# jetson-orin-baseboard.net
KiCad netlist of a schematic drawn in Altium Designer
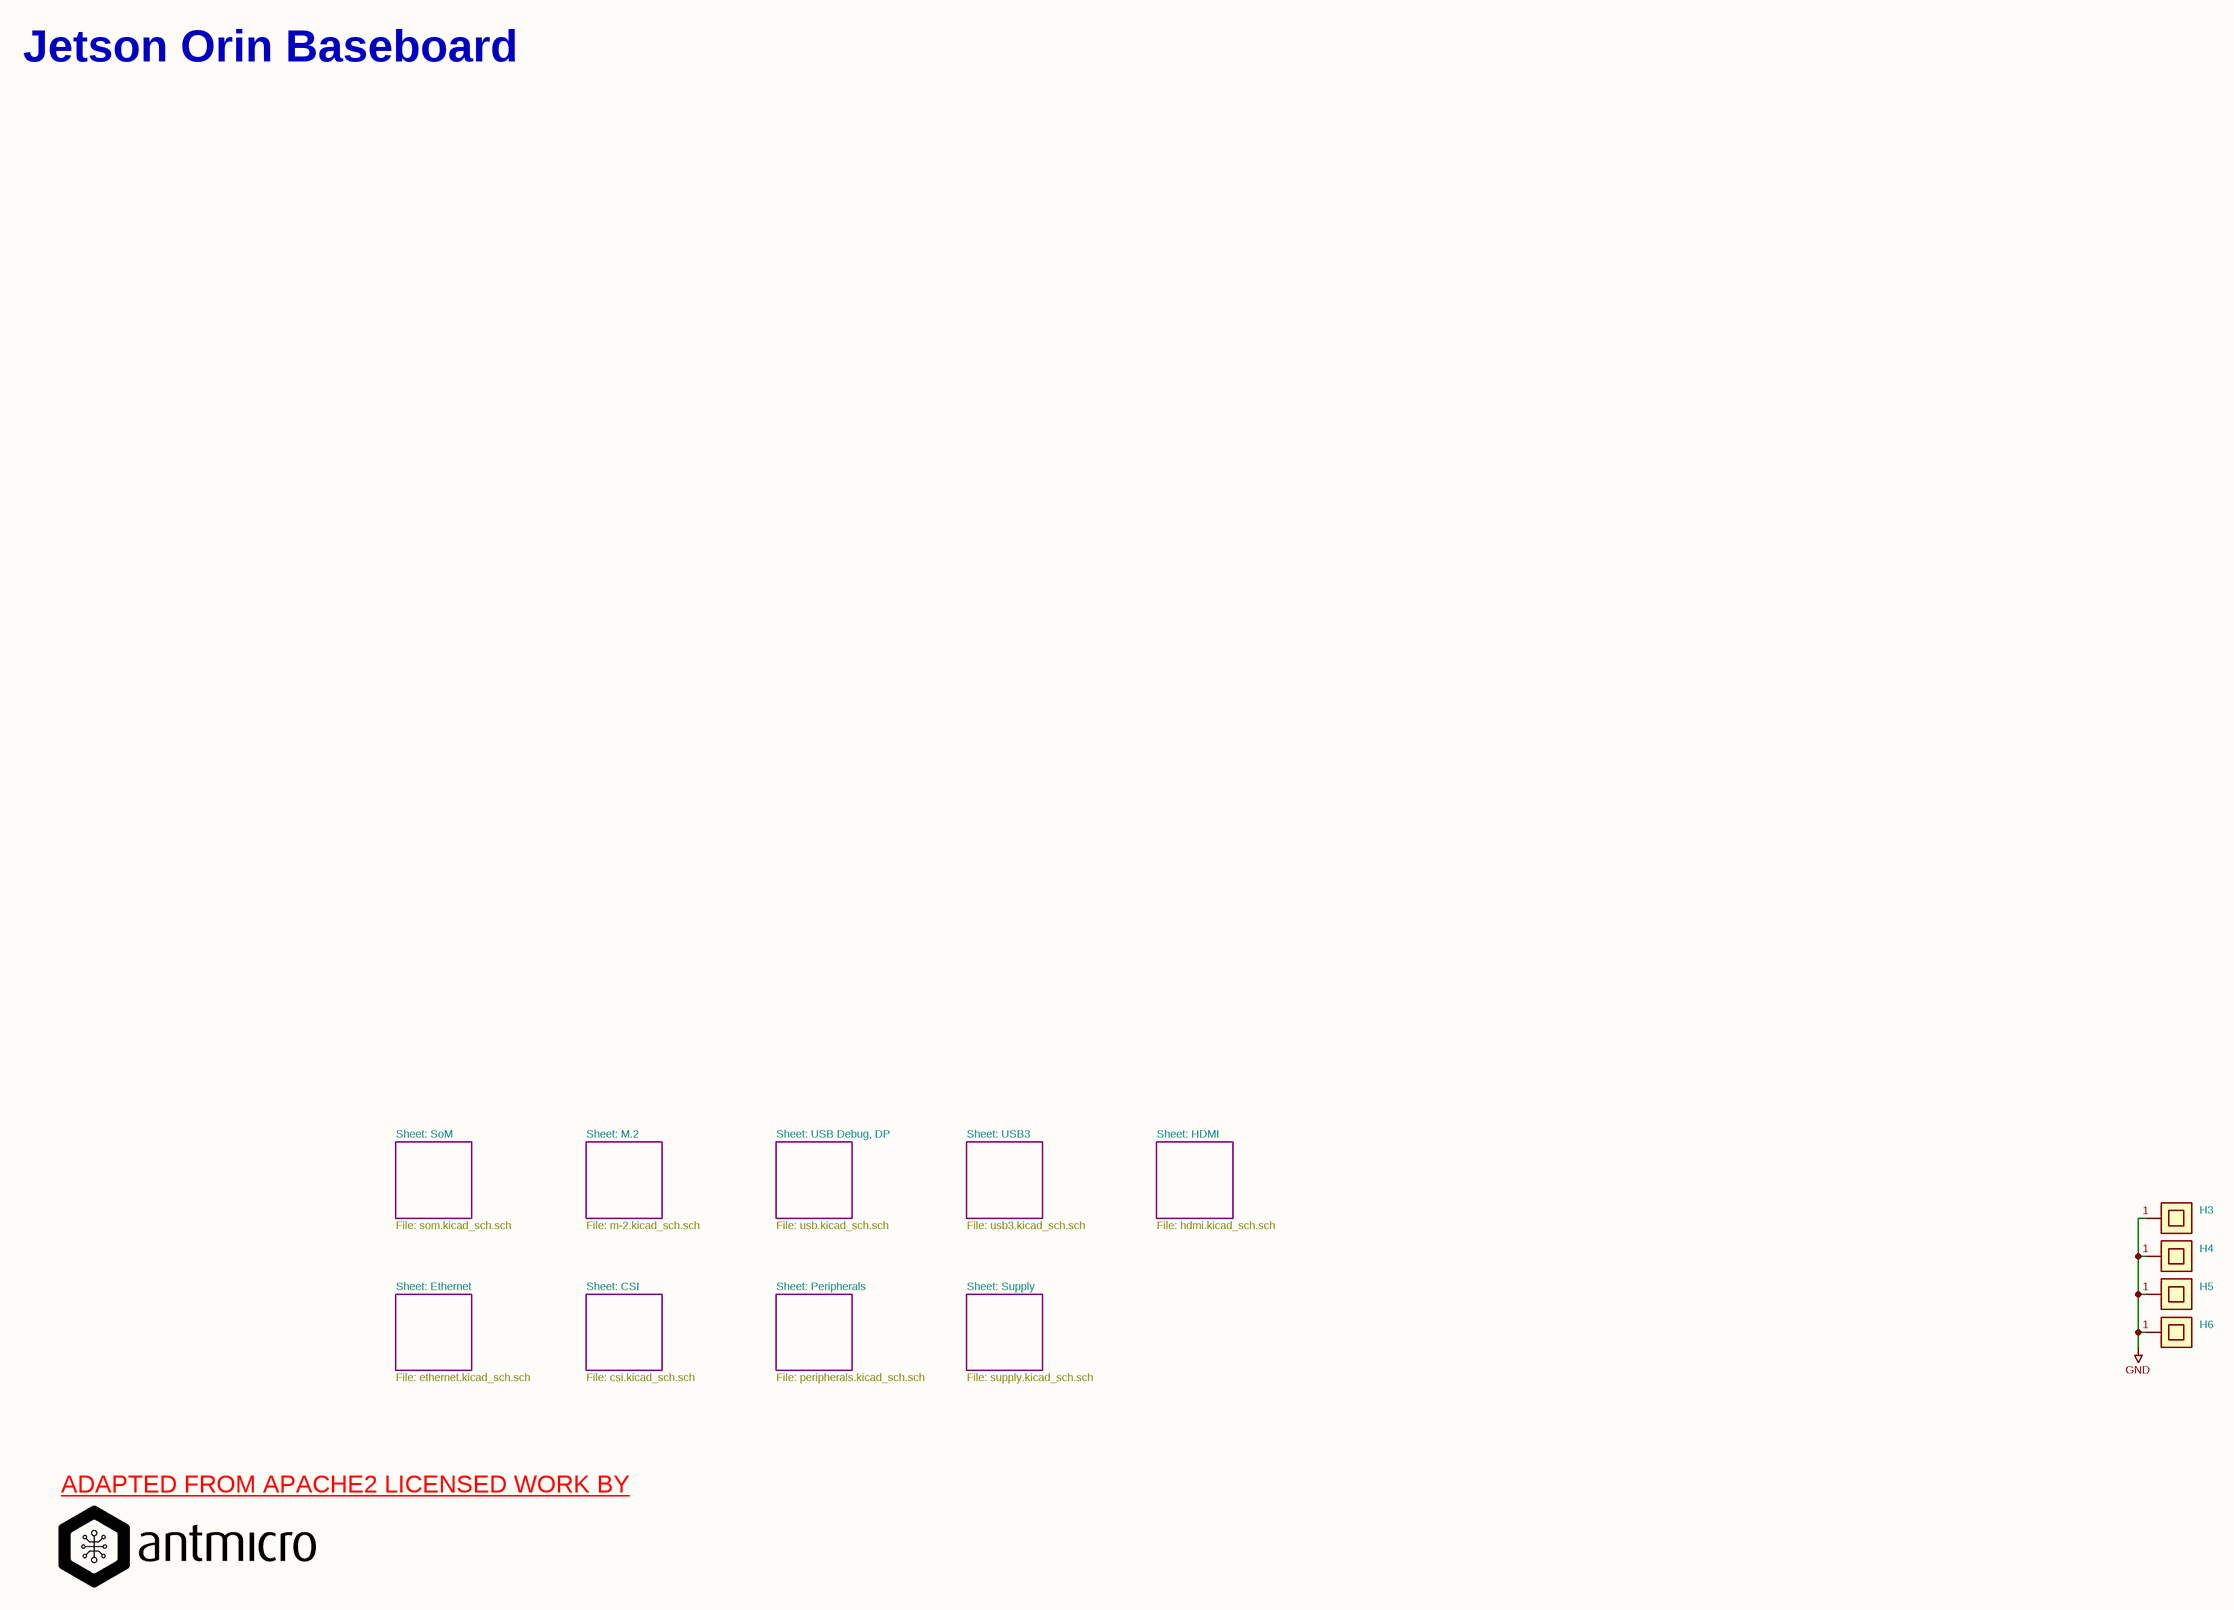
[diagram p0: jetson-orin-baseboard.SchDoc]

(export (version "E")
  (design (tool "Eeschema 10.0.6"))
  (components
    (comp (ref "H3")
      (value "9774065151R")
      (footprint "Spacer_Drill3.7mm_H6.5mm_9774065151R")
      (fields (field (name "AUTHOR") "Antmicro"))
      (libsource (lib "antmicroMechanicalParts") (part "Spacer_Drill3.7mm_H6.5mm_9774065151R"))
    )
    (comp (ref "H4")
      (value "9774065151R")
      (footprint "Spacer_Drill3.7mm_H6.5mm_9774065151R")
      (fields (field (name "AUTHOR") "Antmicro"))
      (libsource (lib "antmicroMechanicalParts") (part "Spacer_Drill3.7mm_H6.5mm_9774065151R"))
    )
    (comp (ref "H5")
      (value "9774065151R")
      (footprint "Spacer_Drill3.7mm_H6.5mm_9774065151R")
      (fields (field (name "AUTHOR") "Antmicro"))
      (libsource (lib "antmicroMechanicalParts") (part "Spacer_Drill3.7mm_H6.5mm_9774065151R"))
    )
    (comp (ref "H6")
      (value "9774065151R")
      (footprint "Spacer_Drill3.7mm_H6.5mm_9774065151R")
      (fields (field (name "AUTHOR") "Antmicro"))
      (libsource (lib "antmicroMechanicalParts") (part "Spacer_Drill3.7mm_H6.5mm_9774065151R"))
    )
  )
  (nets
    (net (code "1") (name "GND") (class "Default")
      (node (ref "H3") (pin "1") (pinfunction "1_1") (pintype "passive"))
      (node (ref "H4") (pin "1") (pinfunction "1_1") (pintype "passive"))
      (node (ref "H5") (pin "1") (pinfunction "1_1") (pintype "passive"))
      (node (ref "H6") (pin "1") (pinfunction "1_1") (pintype "passive"))
    )
  )
)
